# power.net
KiCad netlist of a schematic drawn in Altium Designer
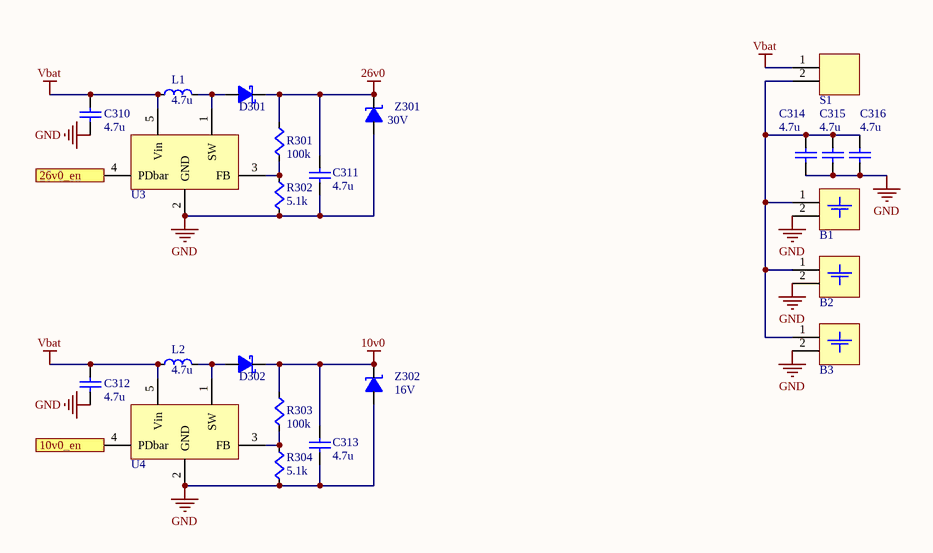
[diagram p0: power.SchDoc]

(export (version "E")
  (design (tool "Eeschema 10.0.6"))
  (components
    (comp (ref "B1") (value "Batt") (footprint "batt_pads") (libsource (lib "Components") (part "Batt")))
    (comp (ref "B2") (value "Batt") (footprint "batt_pads") (libsource (lib "Components") (part "Batt")))
    (comp (ref "B3") (value "Batt") (footprint "batt_pads") (libsource (lib "Components") (part "Batt")))
    (comp (ref "C310")
      (value "4.7u")
      (footprint "SMD0603_cap")
      (description "Ceramic Chip Capacitor")
      (fields (field (name "Comment") "Cap"))
      (libsource (lib "Components") (part "Capacitor Ceramic"))
    )
    (comp (ref "C311")
      (value "4.7u")
      (footprint "SMD0603_cap")
      (description "Ceramic Chip Capacitor")
      (fields (field (name "Comment") "Cap"))
      (libsource (lib "Components") (part "Capacitor Ceramic"))
    )
    (comp (ref "C312")
      (value "4.7u")
      (footprint "SMD0603_cap")
      (description "Ceramic Chip Capacitor")
      (fields (field (name "Comment") "Cap"))
      (libsource (lib "Components") (part "Capacitor Ceramic"))
    )
    (comp (ref "C313")
      (value "4.7u")
      (footprint "SMD0603_cap")
      (description "Ceramic Chip Capacitor")
      (fields (field (name "Comment") "Cap"))
      (libsource (lib "Components") (part "Capacitor Ceramic"))
    )
    (comp (ref "C314")
      (value "4.7u")
      (footprint "SMD0603_cap")
      (description "Ceramic Chip Capacitor")
      (fields (field (name "Comment") "Cap"))
      (libsource (lib "Components") (part "Capacitor Ceramic"))
    )
    (comp (ref "C315")
      (value "4.7u")
      (footprint "SMD0603_cap")
      (description "Ceramic Chip Capacitor")
      (fields (field (name "Comment") "Cap"))
      (libsource (lib "Components") (part "Capacitor Ceramic"))
    )
    (comp (ref "C316")
      (value "4.7u")
      (footprint "SMD0603_cap")
      (description "Ceramic Chip Capacitor")
      (fields (field (name "Comment") "Cap"))
      (libsource (lib "Components") (part "Capacitor Ceramic"))
    )
    (comp (ref "D301")
      (value "Shottky")
      (footprint "sod-323f")
      (libsource (lib "Components") (part "Shottky"))
    )
    (comp (ref "D302")
      (value "Shottky")
      (footprint "sod-323f")
      (libsource (lib "Components") (part "Shottky"))
    )
    (comp (ref "L1")
      (value "4.7u")
      (footprint "smd_0806")
      (description "Inductor")
      (fields (field (name "PUBLISHER") "Altium Limited"))
      (libsource (lib "Components") (part "Inductor"))
    )
    (comp (ref "L2")
      (value "4.7u")
      (footprint "smd_0806")
      (description "Inductor")
      (fields (field (name "PUBLISHER") "Altium Limited"))
      (libsource (lib "Components") (part "Inductor"))
    )
    (comp (ref "R301")
      (value "100k")
      (footprint "SMD0603")
      (description "Resistor")
      (fields (field (name "Comment") "Res"))
      (libsource (lib "Components") (part "Resistor"))
    )
    (comp (ref "R302")
      (value "5.1k")
      (footprint "SMD0603")
      (description "Resistor")
      (fields (field (name "Comment") "Res"))
      (libsource (lib "Components") (part "Resistor"))
    )
    (comp (ref "R303")
      (value "100k")
      (footprint "SMD0603")
      (description "Resistor")
      (fields (field (name "Comment") "Res"))
      (libsource (lib "Components") (part "Resistor"))
    )
    (comp (ref "R304")
      (value "5.1k")
      (footprint "SMD0603")
      (description "Resistor")
      (fields (field (name "Comment") "Res"))
      (libsource (lib "Components") (part "Resistor"))
    )
    (comp (ref "S1")
      (value "Header_smd-2x1")
      (footprint "header_smd-2x1")
      (libsource (lib "Components") (part "Header_smd-2x1"))
    )
    (comp (ref "U3")
      (value "AP3012")
      (footprint "SOT23-5Lead")
      (libsource (lib "Components") (part "AP3012"))
    )
    (comp (ref "U4")
      (value "AP3012")
      (footprint "SOT23-5Lead")
      (libsource (lib "Components") (part "AP3012"))
    )
    (comp (ref "Z301")
      (value "30V")
      (footprint "SOD-323F")
      (fields (field (name "Comment") "Zener"))
      (libsource (lib "Components") (part "Zener"))
    )
    (comp (ref "Z302")
      (value "16V")
      (footprint "SOD-323F")
      (fields (field (name "Comment") "Zener"))
      (libsource (lib "Components") (part "Zener"))
    )
  )
  (nets
    (net (code "1") (name "/10v0_en") (class "Default")
      (node (ref "U4") (pin "4") (pinfunction "PDbar_4") (pintype "passive"))
    )
    (net (code "2") (name "/26v0_en") (class "Default")
      (node (ref "U3") (pin "4") (pinfunction "PDbar_4") (pintype "passive"))
    )
    (net (code "3") (name "10v0") (class "Default")
      (node (ref "C313") (pin "2") (pinfunction "2_2") (pintype "passive"))
      (node (ref "D302") (pin "K") (pinfunction "2_K") (pintype "passive"))
      (node (ref "R303") (pin "2") (pinfunction "2_2") (pintype "passive"))
      (node (ref "Z302") (pin "K") (pinfunction "2_K") (pintype "passive"))
    )
    (net (code "4") (name "26v0") (class "Default")
      (node (ref "C311") (pin "2") (pinfunction "2_2") (pintype "passive"))
      (node (ref "D301") (pin "K") (pinfunction "2_K") (pintype "passive"))
      (node (ref "R301") (pin "2") (pinfunction "2_2") (pintype "passive"))
      (node (ref "Z301") (pin "K") (pinfunction "2_K") (pintype "passive"))
    )
    (net (code "5") (name "GND") (class "Default")
      (node (ref "B1") (pin "2") (pinfunction "2_2") (pintype "passive"))
      (node (ref "B2") (pin "2") (pinfunction "2_2") (pintype "passive"))
      (node (ref "B3") (pin "2") (pinfunction "2_2") (pintype "passive"))
      (node (ref "C310") (pin "1") (pinfunction "1_1") (pintype "passive"))
      (node (ref "C311") (pin "1") (pinfunction "1_1") (pintype "passive"))
      (node (ref "C312") (pin "1") (pinfunction "1_1") (pintype "passive"))
      (node (ref "C313") (pin "1") (pinfunction "1_1") (pintype "passive"))
      (node (ref "C314") (pin "1") (pinfunction "1_1") (pintype "passive"))
      (node (ref "C315") (pin "1") (pinfunction "1_1") (pintype "passive"))
      (node (ref "C316") (pin "1") (pinfunction "1_1") (pintype "passive"))
      (node (ref "R302") (pin "1") (pinfunction "1_1") (pintype "passive"))
      (node (ref "R304") (pin "1") (pinfunction "1_1") (pintype "passive"))
      (node (ref "U3") (pin "2") (pinfunction "GND_2") (pintype "passive"))
      (node (ref "U4") (pin "2") (pinfunction "GND_2") (pintype "passive"))
      (node (ref "Z301") (pin "A") (pintype "passive"))
      (node (ref "Z302") (pin "A") (pintype "passive"))
    )
    (net (code "6") (name "Net-(B1-Pad1)") (class "Default")
      (node (ref "B1") (pin "1") (pinfunction "1_1") (pintype "passive"))
      (node (ref "B2") (pin "1") (pinfunction "1_1") (pintype "passive"))
      (node (ref "B3") (pin "1") (pinfunction "1_1") (pintype "passive"))
      (node (ref "C314") (pin "2") (pinfunction "2_2") (pintype "passive"))
      (node (ref "C315") (pin "2") (pinfunction "2_2") (pintype "passive"))
      (node (ref "C316") (pin "2") (pinfunction "2_2") (pintype "passive"))
      (node (ref "S1") (pin "2") (pinfunction "2_2") (pintype "passive"))
    )
    (net (code "7") (name "Net-(D301-1)") (class "Default")
      (node (ref "D301") (pin "A") (pinfunction "1_A") (pintype "passive"))
      (node (ref "L1") (pin "2") (pinfunction "Source_2") (pintype "passive"))
      (node (ref "U3") (pin "1") (pinfunction "SW_1") (pintype "passive"))
    )
    (net (code "8") (name "Net-(D302-1)") (class "Default")
      (node (ref "D302") (pin "A") (pinfunction "1_A") (pintype "passive"))
      (node (ref "L2") (pin "2") (pinfunction "Source_2") (pintype "passive"))
      (node (ref "U4") (pin "1") (pinfunction "SW_1") (pintype "passive"))
    )
    (net (code "9") (name "Net-(U3-FB)") (class "Default")
      (node (ref "R301") (pin "1") (pinfunction "1_1") (pintype "passive"))
      (node (ref "R302") (pin "2") (pinfunction "2_2") (pintype "passive"))
      (node (ref "U3") (pin "3") (pinfunction "FB_3") (pintype "passive"))
    )
    (net (code "10") (name "Net-(U4-FB)") (class "Default")
      (node (ref "R303") (pin "1") (pinfunction "1_1") (pintype "passive"))
      (node (ref "R304") (pin "2") (pinfunction "2_2") (pintype "passive"))
      (node (ref "U4") (pin "3") (pinfunction "FB_3") (pintype "passive"))
    )
    (net (code "11") (name "Vbat") (class "Default")
      (node (ref "C310") (pin "2") (pinfunction "2_2") (pintype "passive"))
      (node (ref "C312") (pin "2") (pinfunction "2_2") (pintype "passive"))
      (node (ref "L1") (pin "1") (pinfunction "Source_1") (pintype "passive"))
      (node (ref "L2") (pin "1") (pinfunction "Source_1") (pintype "passive"))
      (node (ref "S1") (pin "1") (pinfunction "1_1") (pintype "passive"))
      (node (ref "U3") (pin "5") (pinfunction "Vin_5") (pintype "passive"))
      (node (ref "U4") (pin "5") (pinfunction "Vin_5") (pintype "passive"))
    )
  )
)
